# 6coils-1-discrete.net
KiCad netlist of a schematic drawn in EasyEDA
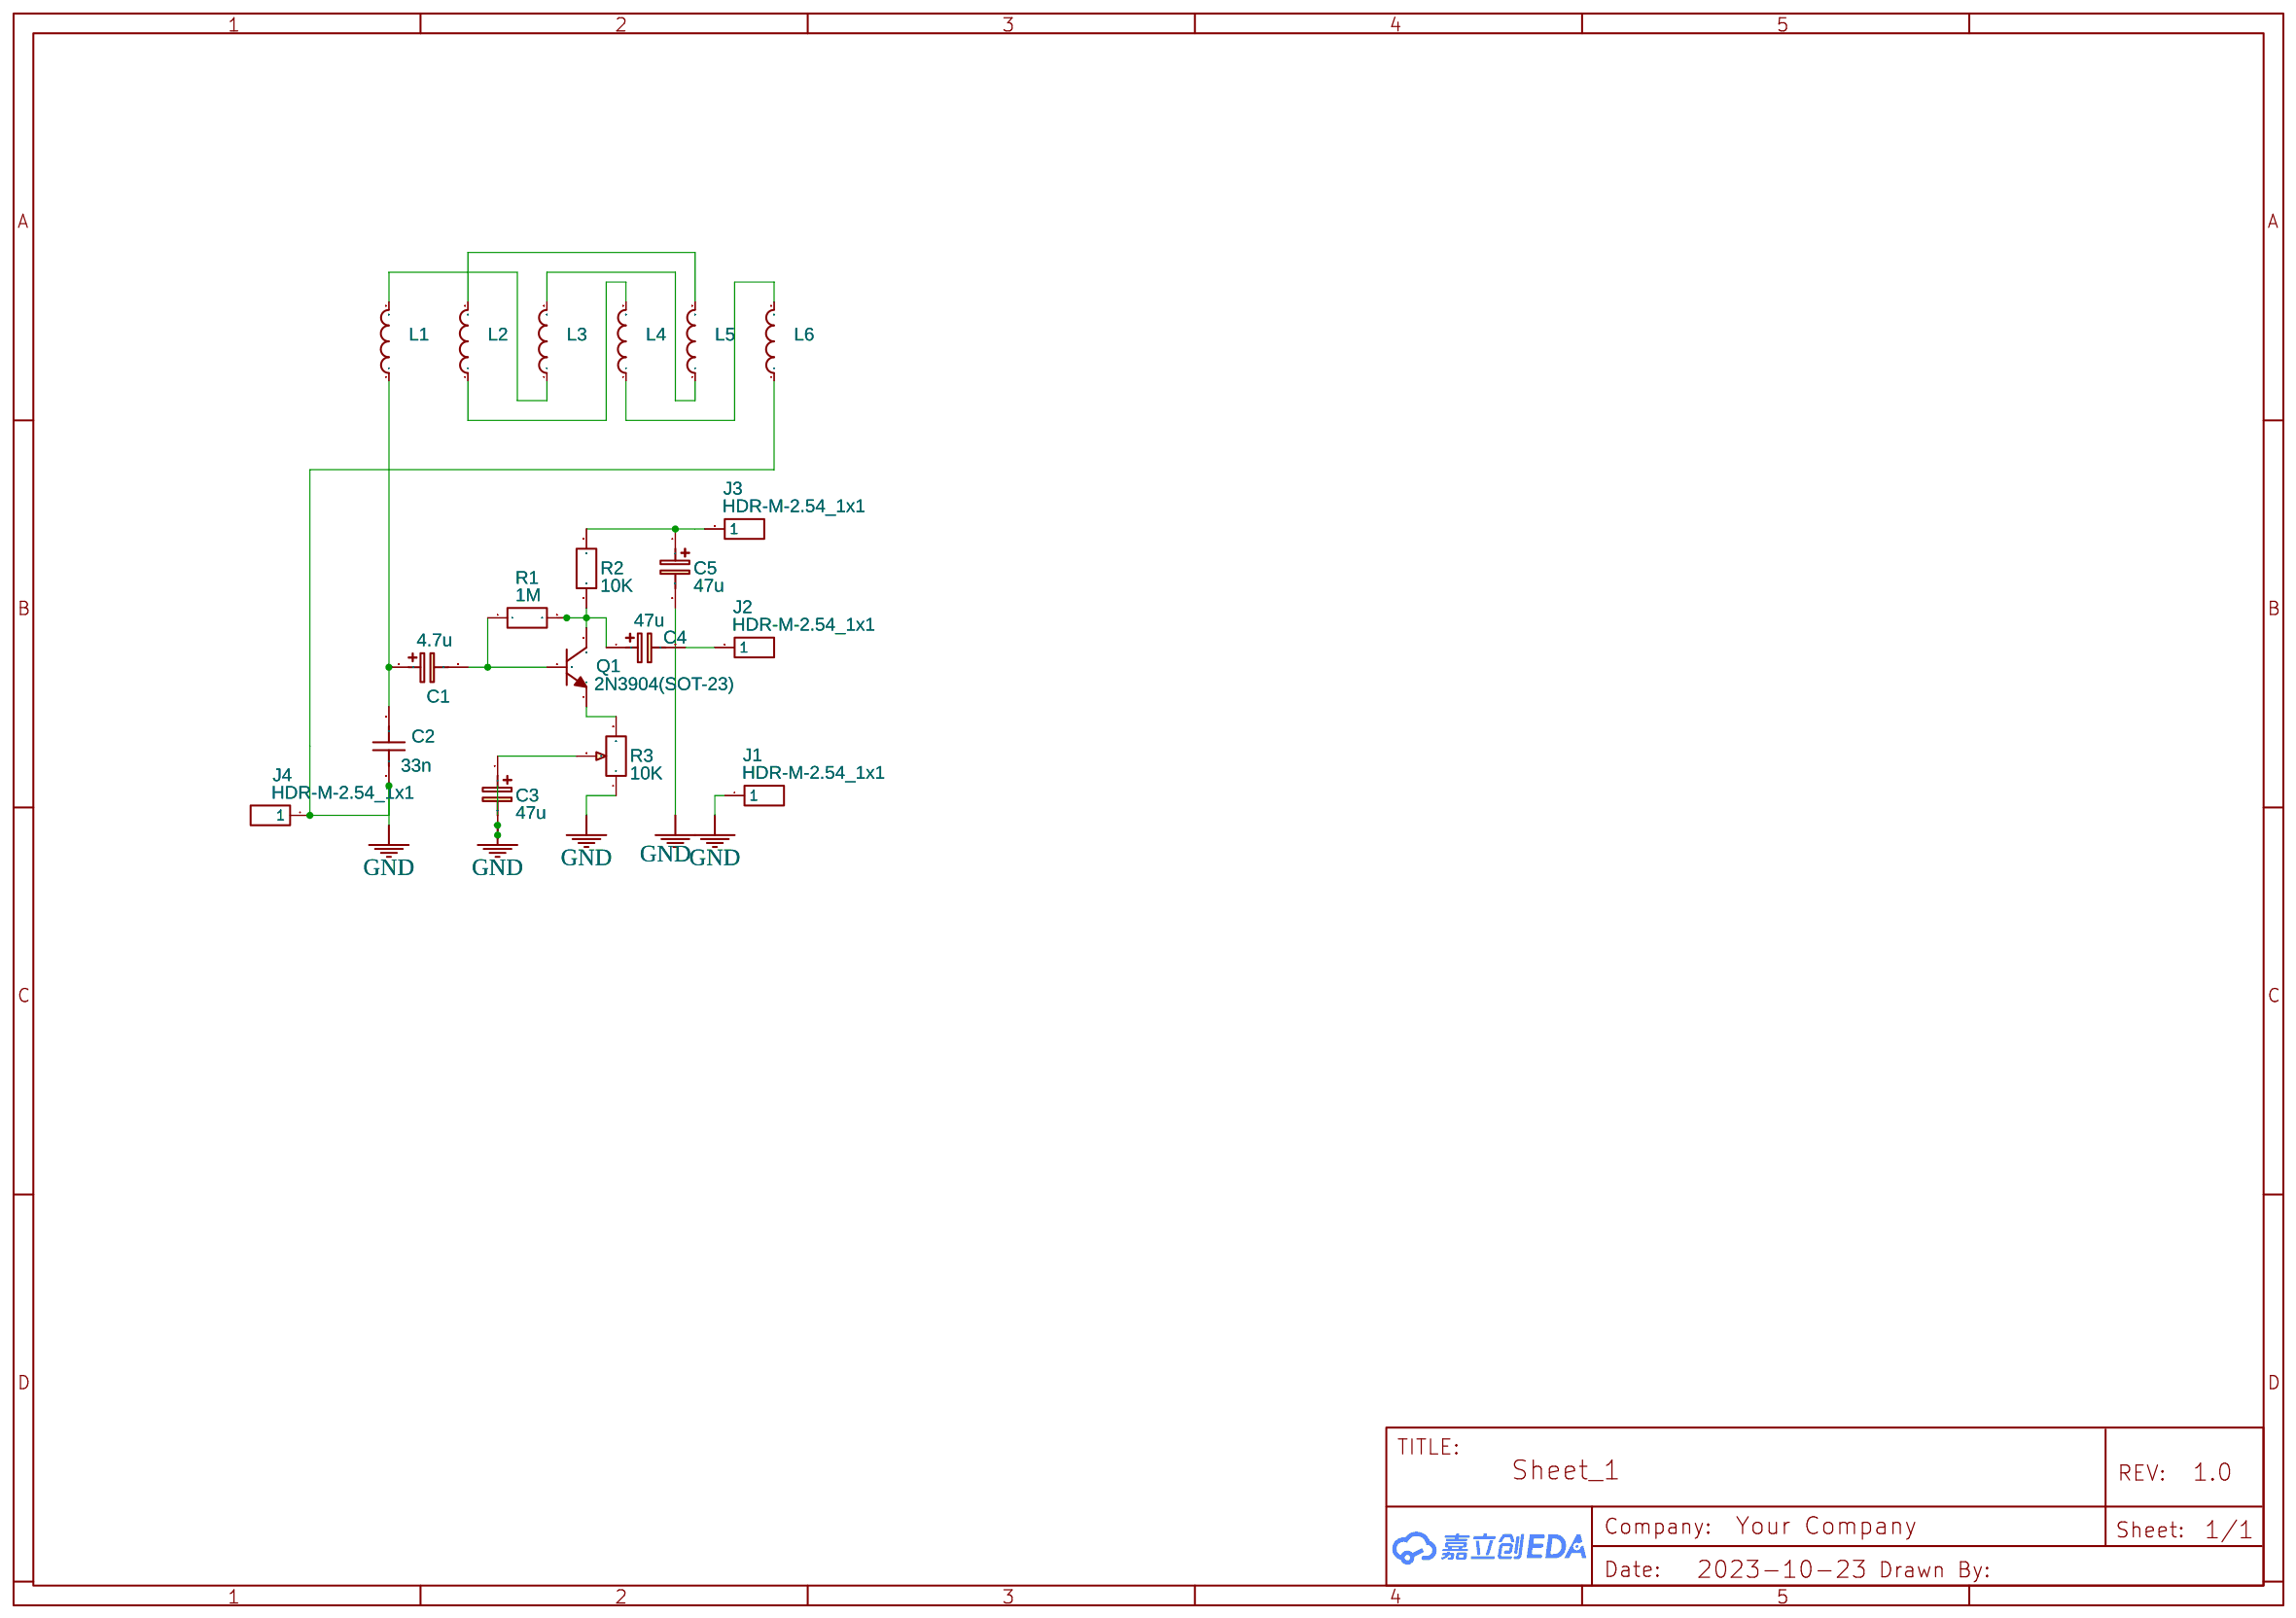
[diagram p0: schematic sheet]

(export (version "E")
  (design (tool "Eeschema 10.0.6"))
  (components
    (comp (ref "C1") (value "4.7u") (libsource (lib "") (part "C_Tan_SMD_A_EU_1")))
    (comp (ref "C2") (value "33n") (libsource (lib "") (part "C_0603_US")))
    (comp (ref "C3") (value "47u") (libsource (lib "") (part "C_Tan_SMD_A_EU")))
    (comp (ref "C4") (value "47u") (libsource (lib "") (part "C_Tan_SMD_A_EU_3")))
    (comp (ref "C5") (value "47u") (libsource (lib "") (part "C_Tan_SMD_A_EU_2")))
    (comp (ref "J1")
      (value "HDR-M-2.54_1x1")
      (fields (field (name "BOM_Supplier Part") "C81276"))
      (libsource (lib "") (part "HDR-M-2.54_1x1"))
    )
    (comp (ref "J2")
      (value "HDR-M-2.54_1x1")
      (fields (field (name "BOM_Supplier Part") "C81276"))
      (libsource (lib "") (part "HDR-M-2.54_1x1"))
    )
    (comp (ref "J3")
      (value "HDR-M-2.54_1x1")
      (fields (field (name "BOM_Supplier Part") "C81276"))
      (libsource (lib "") (part "HDR-M-2.54_1x1"))
    )
    (comp (ref "J4")
      (value "HDR-M-2.54_1x1")
      (fields (field (name "BOM_Supplier Part") "C81276"))
      (libsource (lib "") (part "HDR-M-2.54_1x1_1"))
    )
    (comp (ref "L1")
      (value "INDUCTOR_SMD:L_COILCRAFT_XXL4040")
      (fields (field (name "Manufacturer Part") "Inductor_SMD:L_Coilcraft_XxL4040"))
      (libsource (lib "") (part "INDUCTOR_SMD{colon}L_COILCRAFT_XXL4040_1"))
    )
    (comp (ref "L2")
      (value "INDUCTOR_SMD:L_COILCRAFT_XXL4040")
      (fields (field (name "Manufacturer Part") "Inductor_SMD:L_Coilcraft_XxL4040"))
      (libsource (lib "") (part "INDUCTOR_SMD{colon}L_COILCRAFT_XXL4040_1"))
    )
    (comp (ref "L3")
      (value "INDUCTOR_SMD:L_COILCRAFT_XXL4040")
      (fields (field (name "Manufacturer Part") "Inductor_SMD:L_Coilcraft_XxL4040"))
      (libsource (lib "") (part "INDUCTOR_SMD{colon}L_COILCRAFT_XXL4040"))
    )
    (comp (ref "L4")
      (value "INDUCTOR_SMD:L_COILCRAFT_XXL4040")
      (fields (field (name "Manufacturer Part") "Inductor_SMD:L_Coilcraft_XxL4040"))
      (libsource (lib "") (part "INDUCTOR_SMD{colon}L_COILCRAFT_XXL4040"))
    )
    (comp (ref "L5")
      (value "INDUCTOR_SMD:L_COILCRAFT_XXL4040")
      (fields (field (name "Manufacturer Part") "Inductor_SMD:L_Coilcraft_XxL4040"))
      (libsource (lib "") (part "INDUCTOR_SMD{colon}L_COILCRAFT_XXL4040"))
    )
    (comp (ref "L6")
      (value "INDUCTOR_SMD:L_COILCRAFT_XXL4040")
      (fields (field (name "Manufacturer Part") "Inductor_SMD:L_Coilcraft_XxL4040"))
      (libsource (lib "") (part "INDUCTOR_SMD{colon}L_COILCRAFT_XXL4040"))
    )
    (comp (ref "Q1")
      (value "2N3904(SOT-23)")
      (fields
        (field (name "BOM_Manufacturer Part") "2n3904S-RTK/PS")
        (field (name "BOM_Supplier Part") "C18536")
      )
      (libsource (lib "") (part "2N3904(SOT-23)"))
    )
    (comp (ref "R1") (value "1M") (libsource (lib "") (part "R_0603_EU")))
    (comp (ref "R2") (value "10K") (libsource (lib "") (part "R_0603_EU_1")))
    (comp (ref "R3")
      (value "10K")
      (fields (field (name "Manufacturer Part") "RM063-103 10K") (field (name "Manufacturer") "JML"))
      (libsource (lib "") (part "RM063-103 10K"))
    )
  )
  (nets
    (net (code "1") (name "GND") (class "Default")
      (node (ref "C2") (pin "1") (pinfunction "1_1") (pintype "unspecified"))
      (node (ref "C3") (pin "2") (pinfunction "2_2") (pintype "unspecified"))
      (node (ref "C5") (pin "2") (pinfunction "2_2") (pintype "unspecified"))
      (node (ref "J1") (pin "1") (pinfunction "1_1") (pintype "input"))
      (node (ref "J4") (pin "1") (pinfunction "1_1") (pintype "input"))
      (node (ref "L6") (pin "1") (pinfunction "1_1") (pintype "unspecified"))
      (node (ref "R3") (pin "1") (pinfunction "1_1") (pintype "input"))
    )
    (net (code "2") (name "Net-(C1-Pad1)") (class "Default")
      (node (ref "C1") (pin "1") (pinfunction "1_1") (pintype "unspecified"))
      (node (ref "C2") (pin "2") (pinfunction "2_2") (pintype "unspecified"))
      (node (ref "L1") (pin "1") (pinfunction "1_1") (pintype "unspecified"))
    )
    (net (code "3") (name "Net-(C3-Pad1)") (class "Default")
      (node (ref "C3") (pin "1") (pinfunction "1_1") (pintype "unspecified"))
      (node (ref "R3") (pin "2") (pinfunction "2_2") (pintype "input"))
    )
    (net (code "4") (name "Net-(C4-Pad2)") (class "Default")
      (node (ref "C4") (pin "2") (pinfunction "2_2") (pintype "unspecified"))
      (node (ref "J2") (pin "1") (pinfunction "1_1") (pintype "input"))
    )
    (net (code "5") (name "Net-(C5-Pad1)") (class "Default")
      (node (ref "C5") (pin "1") (pinfunction "1_1") (pintype "unspecified"))
      (node (ref "J3") (pin "1") (pinfunction "1_1") (pintype "input"))
      (node (ref "R2") (pin "2") (pinfunction "2_2") (pintype "unspecified"))
    )
    (net (code "6") (name "Net-(L1-Pad2)") (class "Default")
      (node (ref "L1") (pin "2") (pinfunction "2_2") (pintype "unspecified"))
      (node (ref "L3") (pin "1") (pinfunction "1_1") (pintype "unspecified"))
    )
    (net (code "7") (name "Net-(L2-Pad1)") (class "Default")
      (node (ref "L2") (pin "1") (pinfunction "1_1") (pintype "unspecified"))
      (node (ref "L4") (pin "2") (pinfunction "2_2") (pintype "unspecified"))
    )
    (net (code "8") (name "Net-(L2-Pad2)") (class "Default")
      (node (ref "L2") (pin "2") (pinfunction "2_2") (pintype "unspecified"))
      (node (ref "L5") (pin "2") (pinfunction "2_2") (pintype "unspecified"))
    )
    (net (code "9") (name "Net-(L3-Pad2)") (class "Default")
      (node (ref "L3") (pin "2") (pinfunction "2_2") (pintype "unspecified"))
      (node (ref "L5") (pin "1") (pinfunction "1_1") (pintype "unspecified"))
    )
    (net (code "10") (name "Net-(L4-Pad1)") (class "Default")
      (node (ref "L4") (pin "1") (pinfunction "1_1") (pintype "unspecified"))
      (node (ref "L6") (pin "2") (pinfunction "2_2") (pintype "unspecified"))
    )
    (net (code "11") (name "Net-(Q1-B)") (class "Default")
      (node (ref "C1") (pin "2") (pinfunction "2_2") (pintype "unspecified"))
      (node (ref "Q1") (pin "2") (pinfunction "B_2") (pintype "input"))
      (node (ref "R1") (pin "1") (pinfunction "1_1") (pintype "unspecified"))
    )
    (net (code "12") (name "Net-(Q1-C)") (class "Default")
      (node (ref "C4") (pin "1") (pinfunction "1_1") (pintype "unspecified"))
      (node (ref "Q1") (pin "3") (pinfunction "C_3") (pintype "input"))
      (node (ref "R1") (pin "2") (pinfunction "2_2") (pintype "unspecified"))
      (node (ref "R2") (pin "1") (pinfunction "1_1") (pintype "unspecified"))
    )
    (net (code "13") (name "Net-(Q1-E)") (class "Default")
      (node (ref "Q1") (pin "1") (pinfunction "E_1") (pintype "input"))
      (node (ref "R3") (pin "3") (pinfunction "3_3") (pintype "input"))
    )
  )
)
